# rx-audio_breakout.net
KiCad netlist of a schematic drawn in EAGLE
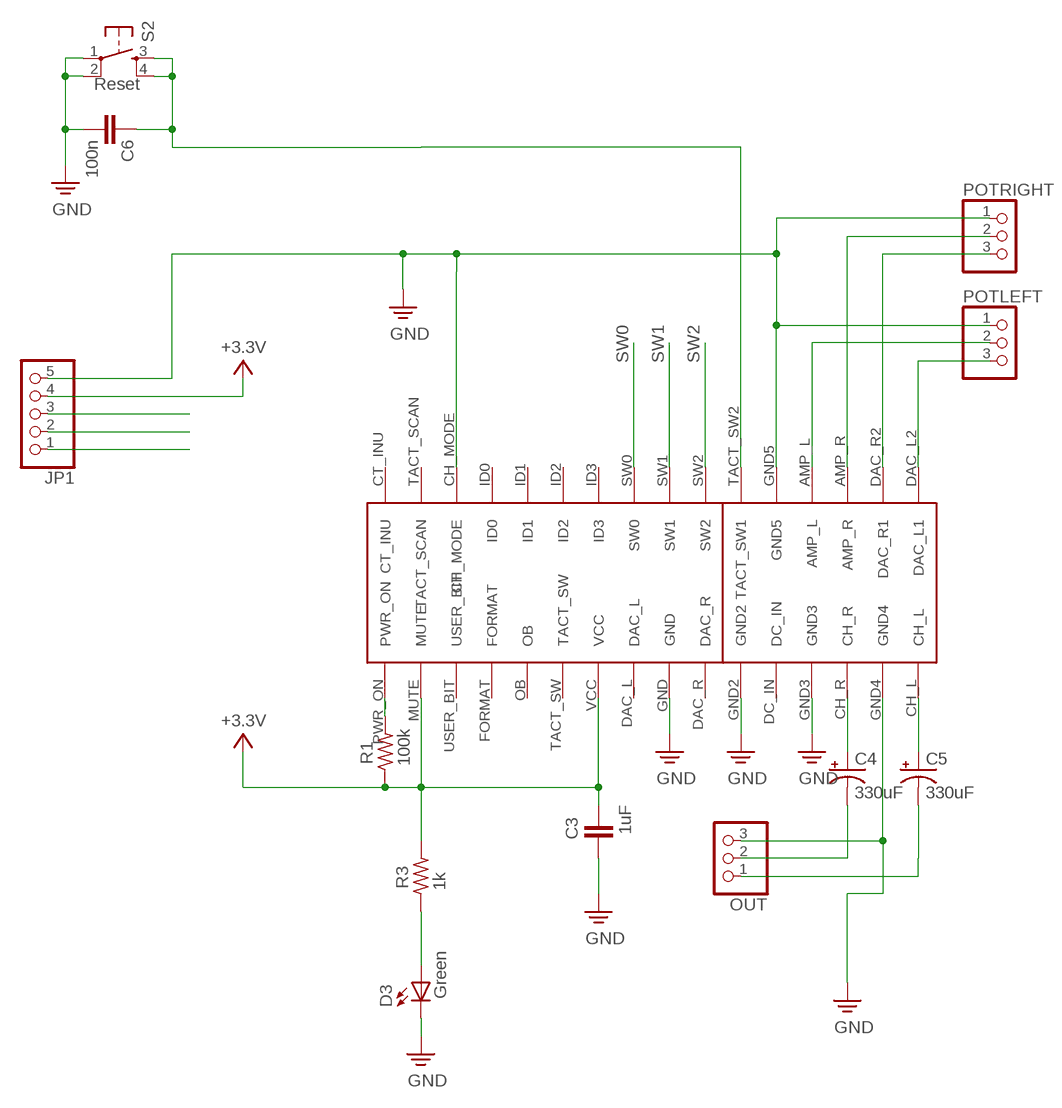
[diagram p0: schematic, sheet 1]

(export (version "E")
  (design (tool "Eeschema 10.0.6"))
  (components
    (comp (ref "C3")
      (value "1uF")
      (footprint "eagle-import:0805A")
      (libsource (lib "eagle-import") (part "CAPACITOR0805"))
    )
    (comp (ref "C4")
      (value "330uF")
      (footprint "eagle-import:SMC_D")
      (libsource (lib "eagle-import") (part "CPOL-USSMCD"))
    )
    (comp (ref "C5")
      (value "330uF")
      (footprint "eagle-import:SMC_D")
      (libsource (lib "eagle-import") (part "CPOL-USSMCD"))
    )
    (comp (ref "C6")
      (value "100n")
      (footprint "eagle-import:C0805")
      (libsource (lib "eagle-import") (part "C-EUC0805"))
    )
    (comp (ref "D3")
      (value "Green")
      (footprint "eagle-import:LED-0603")
      (libsource (lib "eagle-import") (part "LED0603"))
    )
    (comp (ref "JP1")
      (value "PINHD-1X5")
      (footprint "eagle-import:1X05")
      (libsource (lib "eagle-import") (part "PINHD-1X5"))
    )
    (comp (ref "OUT")
      (value "PINHD-1X3")
      (footprint "eagle-import:1X03")
      (libsource (lib "eagle-import") (part "PINHD-1X3"))
    )
    (comp (ref "POTLEFT")
      (value "PINHD-1X3")
      (footprint "eagle-import:1X03")
      (libsource (lib "eagle-import") (part "PINHD-1X3"))
    )
    (comp (ref "POTRIGHT")
      (value "PINHD-1X3")
      (footprint "eagle-import:1X03")
      (libsource (lib "eagle-import") (part "PINHD-1X3"))
    )
    (comp (ref "R1")
      (value "100k")
      (footprint "eagle-import:0805A")
      (libsource (lib "eagle-import") (part "RESISTOR0805"))
    )
    (comp (ref "R3")
      (value "1k")
      (footprint "eagle-import:0805A")
      (libsource (lib "eagle-import") (part "RESISTOR0805"))
    )
    (comp (ref "S2")
      (value "Reset")
      (footprint "eagle-import:TACTILE_SWITCH_SMD")
      (libsource (lib "eagle-import") (part "TAC_SWITCHSMD"))
    )
    (comp (ref "U$1")
      (value "RX-AUDIO-2.4VERTICAL")
      (footprint "eagle-import:AUREL_RX-AUDIO-2.4GH-TRH")
      (libsource (lib "eagle-import") (part "RX-AUDIO-2.4VERTICAL"))
    )
  )
  (nets
    (net (code "1") (name "+3.3V") (class "Default")
      (node (ref "C3") (pin "-") (pinfunction "2_-") (pintype "passive"))
      (node (ref "JP1") (pin "4") (pinfunction "4_4") (pintype "passive"))
      (node (ref "R1") (pin "+") (pinfunction "1_+") (pintype "passive"))
      (node (ref "R3") (pin "-") (pinfunction "2_-") (pintype "passive"))
      (node (ref "U$1") (pin "MUTE") (pinfunction "MUTE_MUTE") (pintype "bidirectional"))
      (node (ref "U$1") (pin "VCC") (pinfunction "VCC_VCC") (pintype "bidirectional"))
    )
    (net (code "2") (name "/SW0") (class "Default")
      (node (ref "JP1") (pin "1") (pinfunction "1_1") (pintype "passive"))
      (node (ref "U$1") (pin "SW0") (pinfunction "SW0_SW0") (pintype "bidirectional"))
    )
    (net (code "3") (name "/SW1") (class "Default")
      (node (ref "JP1") (pin "2") (pinfunction "2_2") (pintype "passive"))
      (node (ref "U$1") (pin "SW1") (pinfunction "SW1_SW1") (pintype "bidirectional"))
    )
    (net (code "4") (name "/SW2") (class "Default")
      (node (ref "JP1") (pin "3") (pinfunction "3_3") (pintype "passive"))
      (node (ref "U$1") (pin "SW2") (pinfunction "SW2_SW2") (pintype "bidirectional"))
    )
    (net (code "5") (name "GND") (class "Default")
      (node (ref "C3") (pin "+") (pinfunction "1_+") (pintype "passive"))
      (node (ref "C6") (pin "2") (pinfunction "2_2") (pintype "passive"))
      (node (ref "D3") (pin "C") (pinfunction "C_C") (pintype "passive"))
      (node (ref "JP1") (pin "5") (pinfunction "5_5") (pintype "passive"))
      (node (ref "OUT") (pin "3") (pinfunction "3_3") (pintype "passive"))
      (node (ref "POTLEFT") (pin "1") (pinfunction "1_1") (pintype "passive"))
      (node (ref "POTRIGHT") (pin "1") (pinfunction "1_1") (pintype "passive"))
      (node (ref "S2") (pin "1") (pinfunction "1_1") (pintype "passive"))
      (node (ref "S2") (pin "2") (pinfunction "2_2") (pintype "passive"))
      (node (ref "U$1") (pin "CH_MODE") (pinfunction "CH_MODE_CH_MODE") (pintype "bidirectional"))
      (node (ref "U$1") (pin "GND") (pinfunction "GND_GND") (pintype "bidirectional"))
      (node (ref "U$1") (pin "GND2") (pinfunction "GND2_GND2") (pintype "bidirectional"))
      (node (ref "U$1") (pin "GND3") (pinfunction "GND3_GND3") (pintype "bidirectional"))
      (node (ref "U$1") (pin "GND4") (pinfunction "GND4_GND4") (pintype "bidirectional"))
      (node (ref "U$1") (pin "GND5") (pinfunction "GND5_GND5") (pintype "bidirectional"))
    )
    (net (code "6") (name "Net-(C4-Pad+)") (class "Default")
      (node (ref "C4") (pin "+") (pinfunction "+_+") (pintype "passive"))
      (node (ref "U$1") (pin "CH_R") (pinfunction "CH_R_CH_R") (pintype "bidirectional"))
    )
    (net (code "7") (name "Net-(C4-Pad-)") (class "Default")
      (node (ref "C4") (pin "-") (pinfunction "-_-") (pintype "passive"))
      (node (ref "OUT") (pin "2") (pinfunction "2_2") (pintype "passive"))
    )
    (net (code "8") (name "Net-(C5-Pad+)") (class "Default")
      (node (ref "C5") (pin "+") (pinfunction "+_+") (pintype "passive"))
      (node (ref "U$1") (pin "CH_L") (pinfunction "CH_L_CH_L") (pintype "bidirectional"))
    )
    (net (code "9") (name "Net-(C5-Pad-)") (class "Default")
      (node (ref "C5") (pin "-") (pinfunction "-_-") (pintype "passive"))
      (node (ref "OUT") (pin "1") (pinfunction "1_1") (pintype "passive"))
    )
    (net (code "10") (name "Net-(POTLEFT-Pad2)") (class "Default")
      (node (ref "POTLEFT") (pin "2") (pinfunction "2_2") (pintype "passive"))
      (node (ref "U$1") (pin "AMP_L") (pinfunction "AMP_L_AMP_L") (pintype "bidirectional"))
    )
    (net (code "11") (name "Net-(POTRIGHT-Pad2)") (class "Default")
      (node (ref "POTRIGHT") (pin "2") (pinfunction "2_2") (pintype "passive"))
      (node (ref "U$1") (pin "AMP_R") (pinfunction "AMP_R_AMP_R") (pintype "bidirectional"))
    )
    (net (code "12") (name "Net-(R1-2)") (class "Default")
      (node (ref "R1") (pin "-") (pinfunction "2_-") (pintype "passive"))
      (node (ref "U$1") (pin "PWR_ON") (pinfunction "PWR_ON_PWR_ON") (pintype "bidirectional"))
    )
    (net (code "13") (name "Net-(R3-1)") (class "Default")
      (node (ref "D3") (pin "A") (pinfunction "A_A") (pintype "passive"))
      (node (ref "R3") (pin "+") (pinfunction "1_+") (pintype "passive"))
    )
    (net (code "14") (name "Net-(U$1-DAC_L1)") (class "Default")
      (node (ref "POTLEFT") (pin "3") (pinfunction "3_3") (pintype "passive"))
      (node (ref "U$1") (pin "DAC_L2") (pinfunction "DAC_L1_DAC_L2") (pintype "bidirectional"))
    )
    (net (code "15") (name "Net-(U$1-DAC_R1)") (class "Default")
      (node (ref "POTRIGHT") (pin "3") (pinfunction "3_3") (pintype "passive"))
      (node (ref "U$1") (pin "DAC_R2") (pinfunction "DAC_R1_DAC_R2") (pintype "bidirectional"))
    )
    (net (code "16") (name "Net-(U$1-TACT_SW1)") (class "Default")
      (node (ref "C6") (pin "1") (pinfunction "1_1") (pintype "passive"))
      (node (ref "S2") (pin "3") (pinfunction "3_3") (pintype "passive"))
      (node (ref "S2") (pin "4") (pinfunction "4_4") (pintype "passive"))
      (node (ref "U$1") (pin "TACT_SW2") (pinfunction "TACT_SW1_TACT_SW2") (pintype "bidirectional"))
    )
    (net (code "17") (name "unconnected-(U$1-PadCT_INU)") (class "Default")
      (node (ref "U$1") (pin "CT_INU") (pinfunction "CT_INU_CT_INU") (pintype "bidirectional"))
    )
    (net (code "18") (name "unconnected-(U$1-PadDAC_L)") (class "Default")
      (node (ref "U$1") (pin "DAC_L") (pinfunction "DAC_L_DAC_L") (pintype "bidirectional"))
    )
    (net (code "19") (name "unconnected-(U$1-PadDAC_R)") (class "Default")
      (node (ref "U$1") (pin "DAC_R") (pinfunction "DAC_R_DAC_R") (pintype "bidirectional"))
    )
    (net (code "20") (name "unconnected-(U$1-PadDC_IN)") (class "Default")
      (node (ref "U$1") (pin "DC_IN") (pinfunction "DC_IN_DC_IN") (pintype "bidirectional"))
    )
    (net (code "21") (name "unconnected-(U$1-PadFORMAT)") (class "Default")
      (node (ref "U$1") (pin "FORMAT") (pinfunction "FORMAT_FORMAT") (pintype "bidirectional"))
    )
    (net (code "22") (name "unconnected-(U$1-PadID0)") (class "Default")
      (node (ref "U$1") (pin "ID0") (pinfunction "ID0_ID0") (pintype "bidirectional"))
    )
    (net (code "23") (name "unconnected-(U$1-PadID1)") (class "Default")
      (node (ref "U$1") (pin "ID1") (pinfunction "ID1_ID1") (pintype "bidirectional"))
    )
    (net (code "24") (name "unconnected-(U$1-PadID2)") (class "Default")
      (node (ref "U$1") (pin "ID2") (pinfunction "ID2_ID2") (pintype "bidirectional"))
    )
    (net (code "25") (name "unconnected-(U$1-PadID3)") (class "Default")
      (node (ref "U$1") (pin "ID3") (pinfunction "ID3_ID3") (pintype "bidirectional"))
    )
    (net (code "26") (name "unconnected-(U$1-PadOB)") (class "Default")
      (node (ref "U$1") (pin "OB") (pinfunction "OB_OB") (pintype "bidirectional"))
    )
    (net (code "27") (name "unconnected-(U$1-PadTACT_SCAN)") (class "Default")
      (node (ref "U$1") (pin "TACT_SCAN") (pinfunction "TACT_SCAN_TACT_SCAN") (pintype "bidirectional"))
    )
    (net (code "28") (name "unconnected-(U$1-PadTACT_SW)") (class "Default")
      (node (ref "U$1") (pin "TACT_SW") (pinfunction "TACT_SW_TACT_SW") (pintype "bidirectional"))
    )
    (net (code "29") (name "unconnected-(U$1-PadUSER_BIT)") (class "Default")
      (node (ref "U$1") (pin "USER_BIT") (pinfunction "USER_BIT_USER_BIT") (pintype "bidirectional"))
    )
  )
)
